# Final-V-0_1.net
KiCad netlist of a schematic drawn in EAGLE
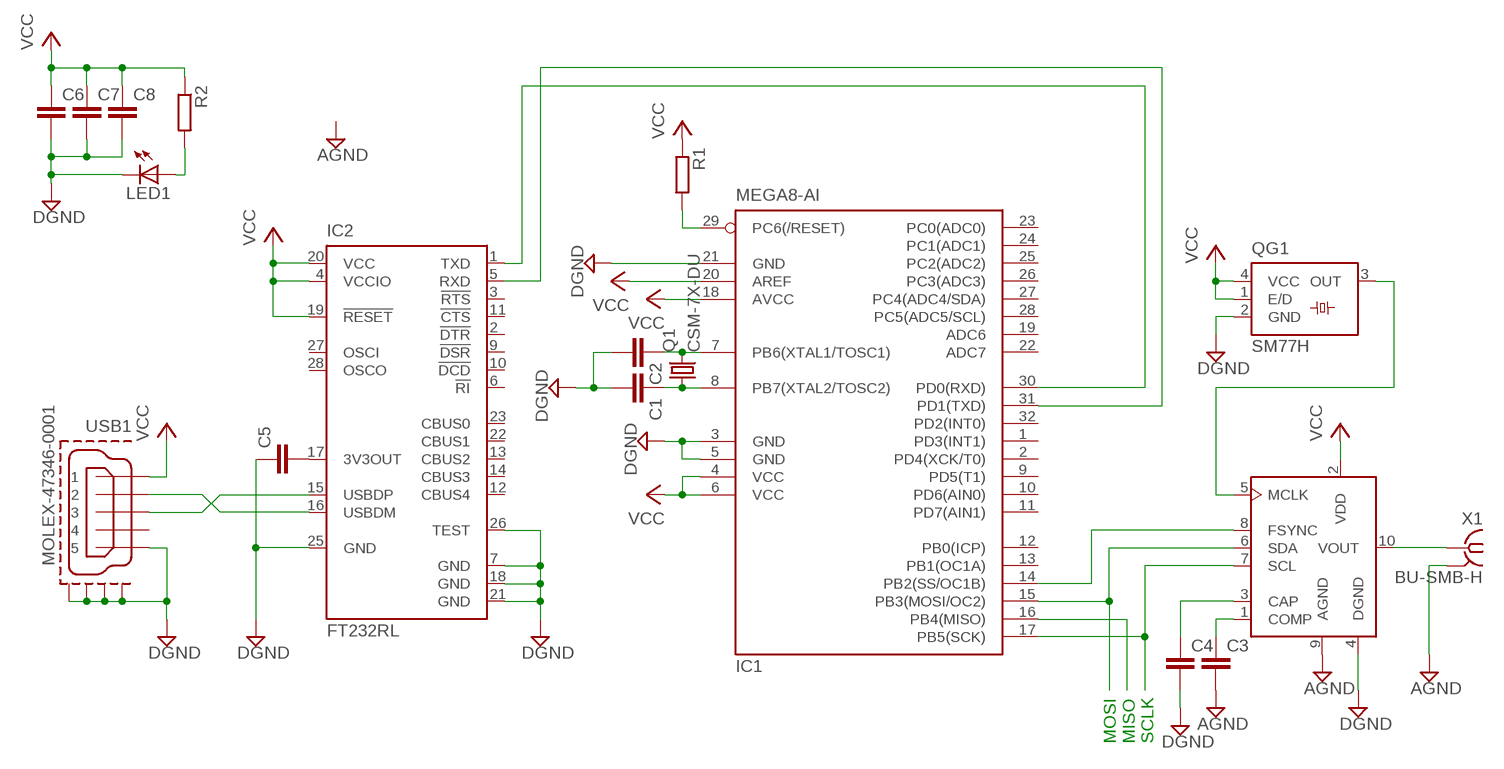
[diagram p0: schematic, sheet 1]

(export (version "E")
  (design (tool "Eeschema 10.0.6"))
  (components
    (comp (ref "C1")
      (value "C-EUC1206K")
      (footprint "eagle-import:C1206K")
      (libsource (lib "eagle-import") (part "C-EUC1206K"))
    )
    (comp (ref "C2")
      (value "C-EUC1206K")
      (footprint "eagle-import:C1206K")
      (libsource (lib "eagle-import") (part "C-EUC1206K"))
    )
    (comp (ref "C3")
      (value "C-EUC1206K")
      (footprint "eagle-import:C1206K")
      (libsource (lib "eagle-import") (part "C-EUC1206K"))
    )
    (comp (ref "C4")
      (value "C-EUC1206K")
      (footprint "eagle-import:C1206K")
      (libsource (lib "eagle-import") (part "C-EUC1206K"))
    )
    (comp (ref "C5")
      (value "C-EUC1206K")
      (footprint "eagle-import:C1206K")
      (libsource (lib "eagle-import") (part "C-EUC1206K"))
    )
    (comp (ref "C6")
      (value "C-EUC1206K")
      (footprint "eagle-import:C1206K")
      (libsource (lib "eagle-import") (part "C-EUC1206K"))
    )
    (comp (ref "C7")
      (value "C-EUC1206K")
      (footprint "eagle-import:C1206K")
      (libsource (lib "eagle-import") (part "C-EUC1206K"))
    )
    (comp (ref "C8")
      (value "C-EUC1206K")
      (footprint "eagle-import:C1206K")
      (libsource (lib "eagle-import") (part "C-EUC1206K"))
    )
    (comp (ref "IC1")
      (value "MEGA8-AI")
      (footprint "eagle-import:TQFP32-08")
      (fields (field (name "MPN") "ATMEGA8-16AU"))
      (libsource (lib "eagle-import") (part "MEGA8-AI"))
    )
    (comp (ref "IC2")
      (value "FT232RL")
      (footprint "eagle-import:SSOP28")
      (libsource (lib "eagle-import") (part "FT232RL"))
    )
    (comp (ref "LED1")
      (value "LEDSML1206")
      (footprint "eagle-import:SML1206")
      (libsource (lib "eagle-import") (part "LEDSML1206"))
    )
    (comp (ref "Q1")
      (value "CSM-7X-DU")
      (footprint "eagle-import:CSM-7X-DU")
      (libsource (lib "eagle-import") (part "CSM-7X-DU"))
    )
    (comp (ref "QG1")
      (value "SM77H")
      (footprint "eagle-import:SM77H")
      (libsource (lib "eagle-import") (part "SM77H"))
    )
    (comp (ref "R1")
      (value "R-EU_M1206")
      (footprint "eagle-import:M1206")
      (libsource (lib "eagle-import") (part "R-EU_M1206"))
    )
    (comp (ref "R2")
      (value "R-EU_M1206")
      (footprint "eagle-import:M1206")
      (libsource (lib "eagle-import") (part "R-EU_M1206"))
    )
    (comp (ref "U$1")
      (value "AD9833-SMD")
      (footprint "eagle-import:MSOP10")
      (libsource (lib "eagle-import") (part "AD9833-SMD"))
    )
    (comp (ref "USB1")
      (value "MOLEX-47346-0001")
      (footprint "eagle-import:MOLEX-47364-0001")
      (libsource (lib "eagle-import") (part "MOLEX-47346-0001"))
    )
    (comp (ref "X1")
      (value "BU-SMB-H")
      (footprint "eagle-import:BU-SMB-H")
      (libsource (lib "eagle-import") (part "BU-SMB-H"))
    )
  )
  (nets
    (net (code "1") (name "AGND") (class "Default")
      (node (ref "C3") (pin "2") (pinfunction "2_2") (pintype "passive"))
      (node (ref "U$1") (pin "9") (pinfunction "AGND_9") (pintype "bidirectional"))
      (node (ref "X1") (pin "2") (pinfunction "2_2") (pintype "passive"))
      (node (ref "X1") (pin "3") (pinfunction "2_3") (pintype "passive"))
      (node (ref "X1") (pin "4") (pinfunction "2_4") (pintype "passive"))
      (node (ref "X1") (pin "5") (pinfunction "2_5") (pintype "passive"))
    )
    (net (code "2") (name "DGND") (class "Default")
      (node (ref "C1") (pin "2") (pinfunction "2_2") (pintype "passive"))
      (node (ref "C2") (pin "2") (pinfunction "2_2") (pintype "passive"))
      (node (ref "C4") (pin "2") (pinfunction "2_2") (pintype "passive"))
      (node (ref "C5") (pin "1") (pinfunction "1_1") (pintype "passive"))
      (node (ref "C6") (pin "2") (pinfunction "2_2") (pintype "passive"))
      (node (ref "C7") (pin "2") (pinfunction "2_2") (pintype "passive"))
      (node (ref "C8") (pin "2") (pinfunction "2_2") (pintype "passive"))
      (node (ref "IC1") (pin "21") (pinfunction "GND_21") (pintype "power_in"))
      (node (ref "IC1") (pin "3") (pinfunction "GND_3") (pintype "power_in"))
      (node (ref "IC1") (pin "5") (pinfunction "GND_5") (pintype "power_in"))
      (node (ref "IC2") (pin "18") (pinfunction "GND_18") (pintype "power_in"))
      (node (ref "IC2") (pin "21") (pinfunction "GND_21") (pintype "power_in"))
      (node (ref "IC2") (pin "25") (pinfunction "GND_25") (pintype "power_in"))
      (node (ref "IC2") (pin "26") (pinfunction "TEST_26") (pintype "input"))
      (node (ref "IC2") (pin "7") (pinfunction "GND_7") (pintype "power_in"))
      (node (ref "LED1") (pin "C") (pinfunction "C_C") (pintype "passive"))
      (node (ref "QG1") (pin "2") (pinfunction "GND_2") (pintype "power_in"))
      (node (ref "U$1") (pin "4") (pinfunction "DGND_4") (pintype "bidirectional"))
      (node (ref "USB1") (pin "5") (pinfunction "5_5") (pintype "input"))
      (node (ref "USB1") (pin "GND1") (pinfunction "GND1_GND1") (pintype "bidirectional"))
      (node (ref "USB1") (pin "GND2") (pinfunction "GND2_GND2") (pintype "bidirectional"))
      (node (ref "USB1") (pin "GND3") (pinfunction "GND3_GND3") (pintype "bidirectional"))
      (node (ref "USB1") (pin "GND4") (pinfunction "GND4_GND4") (pintype "bidirectional"))
    )
    (net (code "3") (name "Net-(IC1-PB2(SS{slash}OC1B))") (class "Default")
      (node (ref "IC1") (pin "14") (pinfunction "PB2(SS/OC1B)_14") (pintype "bidirectional"))
      (node (ref "U$1") (pin "8") (pinfunction "FSYNC_8") (pintype "bidirectional"))
    )
    (net (code "4") (name "Net-(IC1-PB3(MOSI{slash}OC2))") (class "Default")
      (node (ref "IC1") (pin "15") (pinfunction "PB3(MOSI/OC2)_15") (pintype "bidirectional"))
      (node (ref "U$1") (pin "6") (pinfunction "SDA_6") (pintype "bidirectional"))
    )
    (net (code "5") (name "Net-(IC1-PB5(SCK))") (class "Default")
      (node (ref "IC1") (pin "17") (pinfunction "PB5(SCK)_17") (pintype "bidirectional"))
      (node (ref "U$1") (pin "7") (pinfunction "SCL_7") (pintype "bidirectional"))
    )
    (net (code "6") (name "Net-(IC1-PB6(XTAL1{slash}TOSC1))") (class "Default")
      (node (ref "C2") (pin "1") (pinfunction "1_1") (pintype "passive"))
      (node (ref "IC1") (pin "7") (pinfunction "PB6(XTAL1/TOSC1)_7") (pintype "bidirectional"))
      (node (ref "Q1") (pin "2") (pinfunction "2_2") (pintype "passive"))
    )
    (net (code "7") (name "Net-(IC1-PB7(XTAL2{slash}TOSC2))") (class "Default")
      (node (ref "C1") (pin "1") (pinfunction "1_1") (pintype "passive"))
      (node (ref "IC1") (pin "8") (pinfunction "PB7(XTAL2/TOSC2)_8") (pintype "bidirectional"))
      (node (ref "Q1") (pin "1") (pinfunction "1_1") (pintype "passive"))
    )
    (net (code "8") (name "Net-(IC1-PC6({slash}RESET))") (class "Default")
      (node (ref "IC1") (pin "29") (pinfunction "PC6(/RESET)_29") (pintype "bidirectional"))
      (node (ref "R1") (pin "2") (pinfunction "2_2") (pintype "passive"))
    )
    (net (code "9") (name "Net-(IC1-PD0(RXD))") (class "Default")
      (node (ref "IC1") (pin "30") (pinfunction "PD0(RXD)_30") (pintype "bidirectional"))
      (node (ref "IC2") (pin "1") (pinfunction "TXD_1") (pintype "output"))
    )
    (net (code "10") (name "Net-(IC1-PD1(TXD))") (class "Default")
      (node (ref "IC1") (pin "31") (pinfunction "PD1(TXD)_31") (pintype "bidirectional"))
      (node (ref "IC2") (pin "5") (pinfunction "RXD_5") (pintype "input"))
    )
    (net (code "11") (name "Net-(IC2-3V3OUT)") (class "Default")
      (node (ref "C5") (pin "2") (pinfunction "2_2") (pintype "passive"))
      (node (ref "IC2") (pin "17") (pinfunction "3V3OUT_17") (pintype "output"))
    )
    (net (code "12") (name "Net-(IC2-USBDM)") (class "Default")
      (node (ref "IC2") (pin "16") (pinfunction "USBDM_16") (pintype "bidirectional"))
      (node (ref "USB1") (pin "2") (pinfunction "2_2") (pintype "input"))
    )
    (net (code "13") (name "Net-(IC2-USBDP)") (class "Default")
      (node (ref "IC2") (pin "15") (pinfunction "USBDP_15") (pintype "bidirectional"))
      (node (ref "USB1") (pin "3") (pinfunction "3_3") (pintype "input"))
    )
    (net (code "14") (name "Net-(LED1-PadA)") (class "Default")
      (node (ref "LED1") (pin "A") (pinfunction "A_A") (pintype "passive"))
      (node (ref "R2") (pin "2") (pinfunction "2_2") (pintype "passive"))
    )
    (net (code "15") (name "Net-(QG1-OUT)") (class "Default")
      (node (ref "QG1") (pin "3") (pinfunction "OUT_3") (pintype "output"))
      (node (ref "U$1") (pin "5") (pinfunction "MCLK_5") (pintype "bidirectional"))
    )
    (net (code "16") (name "Net-(U$1-CAP)") (class "Default")
      (node (ref "C4") (pin "1") (pinfunction "1_1") (pintype "passive"))
      (node (ref "U$1") (pin "3") (pinfunction "CAP_3") (pintype "bidirectional"))
    )
    (net (code "17") (name "Net-(U$1-COMP)") (class "Default")
      (node (ref "C3") (pin "1") (pinfunction "1_1") (pintype "passive"))
      (node (ref "U$1") (pin "1") (pinfunction "COMP_1") (pintype "bidirectional"))
    )
    (net (code "18") (name "Net-(U$1-VOUT)") (class "Default")
      (node (ref "U$1") (pin "10") (pinfunction "VOUT_10") (pintype "bidirectional"))
      (node (ref "X1") (pin "1") (pinfunction "1_1") (pintype "passive"))
    )
    (net (code "19") (name "VCC") (class "Default")
      (node (ref "C6") (pin "1") (pinfunction "1_1") (pintype "passive"))
      (node (ref "C7") (pin "1") (pinfunction "1_1") (pintype "passive"))
      (node (ref "C8") (pin "1") (pinfunction "1_1") (pintype "passive"))
      (node (ref "IC1") (pin "18") (pinfunction "AVCC_18") (pintype "power_in"))
      (node (ref "IC1") (pin "20") (pinfunction "AREF_20") (pintype "passive"))
      (node (ref "IC1") (pin "4") (pinfunction "VCC_4") (pintype "power_in"))
      (node (ref "IC1") (pin "6") (pinfunction "VCC_6") (pintype "power_in"))
      (node (ref "IC2") (pin "19") (pinfunction "~{RESET}_19") (pintype "input"))
      (node (ref "IC2") (pin "20") (pinfunction "VCC_20") (pintype "power_in"))
      (node (ref "IC2") (pin "4") (pinfunction "VCCIO_4") (pintype "power_in"))
      (node (ref "QG1") (pin "1") (pinfunction "E/D_1") (pintype "input"))
      (node (ref "QG1") (pin "4") (pinfunction "VCC_4") (pintype "power_in"))
      (node (ref "R1") (pin "1") (pinfunction "1_1") (pintype "passive"))
      (node (ref "R2") (pin "1") (pinfunction "1_1") (pintype "passive"))
      (node (ref "U$1") (pin "2") (pinfunction "VDD_2") (pintype "bidirectional"))
      (node (ref "USB1") (pin "1") (pinfunction "1_1") (pintype "input"))
    )
    (net (code "20") (name "unconnected-(IC1-ADC6-Pad19)") (class "Default")
      (node (ref "IC1") (pin "19") (pinfunction "ADC6_19") (pintype "bidirectional"))
    )
    (net (code "21") (name "unconnected-(IC1-ADC7-Pad22)") (class "Default")
      (node (ref "IC1") (pin "22") (pinfunction "ADC7_22") (pintype "bidirectional"))
    )
    (net (code "22") (name "unconnected-(IC1-PB0(ICP)-Pad12)") (class "Default")
      (node (ref "IC1") (pin "12") (pinfunction "PB0(ICP)_12") (pintype "bidirectional"))
    )
    (net (code "23") (name "unconnected-(IC1-PB1(OC1A)-Pad13)") (class "Default")
      (node (ref "IC1") (pin "13") (pinfunction "PB1(OC1A)_13") (pintype "bidirectional"))
    )
    (net (code "24") (name "unconnected-(IC1-PB4(MISO)-Pad16)") (class "Default")
      (node (ref "IC1") (pin "16") (pinfunction "PB4(MISO)_16") (pintype "bidirectional"))
    )
    (net (code "25") (name "unconnected-(IC1-PC0(ADC0)-Pad23)") (class "Default")
      (node (ref "IC1") (pin "23") (pinfunction "PC0(ADC0)_23") (pintype "bidirectional"))
    )
    (net (code "26") (name "unconnected-(IC1-PC1(ADC1)-Pad24)") (class "Default")
      (node (ref "IC1") (pin "24") (pinfunction "PC1(ADC1)_24") (pintype "bidirectional"))
    )
    (net (code "27") (name "unconnected-(IC1-PC2(ADC2)-Pad25)") (class "Default")
      (node (ref "IC1") (pin "25") (pinfunction "PC2(ADC2)_25") (pintype "bidirectional"))
    )
    (net (code "28") (name "unconnected-(IC1-PC3(ADC3)-Pad26)") (class "Default")
      (node (ref "IC1") (pin "26") (pinfunction "PC3(ADC3)_26") (pintype "bidirectional"))
    )
    (net (code "29") (name "unconnected-(IC1-PC4(ADC4{slash}SDA)-Pad27)") (class "Default")
      (node (ref "IC1") (pin "27") (pinfunction "PC4(ADC4/SDA)_27") (pintype "bidirectional"))
    )
    (net (code "30") (name "unconnected-(IC1-PC5(ADC5{slash}SCL)-Pad28)") (class "Default")
      (node (ref "IC1") (pin "28") (pinfunction "PC5(ADC5/SCL)_28") (pintype "bidirectional"))
    )
    (net (code "31") (name "unconnected-(IC1-PD2(INT0)-Pad32)") (class "Default")
      (node (ref "IC1") (pin "32") (pinfunction "PD2(INT0)_32") (pintype "bidirectional"))
    )
    (net (code "32") (name "unconnected-(IC1-PD3(INT1)-Pad1)") (class "Default")
      (node (ref "IC1") (pin "1") (pinfunction "PD3(INT1)_1") (pintype "bidirectional"))
    )
    (net (code "33") (name "unconnected-(IC1-PD4(XCK{slash}T0)-Pad2)") (class "Default")
      (node (ref "IC1") (pin "2") (pinfunction "PD4(XCK/T0)_2") (pintype "bidirectional"))
    )
    (net (code "34") (name "unconnected-(IC1-PD5(T1)-Pad9)") (class "Default")
      (node (ref "IC1") (pin "9") (pinfunction "PD5(T1)_9") (pintype "bidirectional"))
    )
    (net (code "35") (name "unconnected-(IC1-PD6(AIN0)-Pad10)") (class "Default")
      (node (ref "IC1") (pin "10") (pinfunction "PD6(AIN0)_10") (pintype "bidirectional"))
    )
    (net (code "36") (name "unconnected-(IC1-PD7(AIN1)-Pad11)") (class "Default")
      (node (ref "IC1") (pin "11") (pinfunction "PD7(AIN1)_11") (pintype "bidirectional"))
    )
    (net (code "37") (name "unconnected-(IC2-CBUS0-Pad23)") (class "Default")
      (node (ref "IC2") (pin "23") (pinfunction "CBUS0_23") (pintype "bidirectional"))
    )
    (net (code "38") (name "unconnected-(IC2-CBUS1-Pad22)") (class "Default")
      (node (ref "IC2") (pin "22") (pinfunction "CBUS1_22") (pintype "bidirectional"))
    )
    (net (code "39") (name "unconnected-(IC2-CBUS2-Pad13)") (class "Default")
      (node (ref "IC2") (pin "13") (pinfunction "CBUS2_13") (pintype "bidirectional"))
    )
    (net (code "40") (name "unconnected-(IC2-CBUS3-Pad14)") (class "Default")
      (node (ref "IC2") (pin "14") (pinfunction "CBUS3_14") (pintype "bidirectional"))
    )
    (net (code "41") (name "unconnected-(IC2-CBUS4-Pad12)") (class "Default")
      (node (ref "IC2") (pin "12") (pinfunction "CBUS4_12") (pintype "bidirectional"))
    )
    (net (code "42") (name "unconnected-(IC2-OSCI-Pad27)") (class "Default")
      (node (ref "IC2") (pin "27") (pinfunction "OSCI_27") (pintype "input"))
    )
    (net (code "43") (name "unconnected-(IC2-OSCO-Pad28)") (class "Default")
      (node (ref "IC2") (pin "28") (pinfunction "OSCO_28") (pintype "output"))
    )
    (net (code "44") (name "unconnected-(IC2-~{CTS}-Pad11)") (class "Default")
      (node (ref "IC2") (pin "11") (pinfunction "~{CTS}_11") (pintype "input"))
    )
    (net (code "45") (name "unconnected-(IC2-~{DCD}-Pad10)") (class "Default")
      (node (ref "IC2") (pin "10") (pinfunction "~{DCD}_10") (pintype "input"))
    )
    (net (code "46") (name "unconnected-(IC2-~{DSR}-Pad9)") (class "Default")
      (node (ref "IC2") (pin "9") (pinfunction "~{DSR}_9") (pintype "input"))
    )
    (net (code "47") (name "unconnected-(IC2-~{DTR}-Pad2)") (class "Default")
      (node (ref "IC2") (pin "2") (pinfunction "~{DTR}_2") (pintype "output"))
    )
    (net (code "48") (name "unconnected-(IC2-~{RI}-Pad6)") (class "Default")
      (node (ref "IC2") (pin "6") (pinfunction "~{RI}_6") (pintype "input"))
    )
    (net (code "49") (name "unconnected-(IC2-~{RTS}-Pad3)") (class "Default")
      (node (ref "IC2") (pin "3") (pinfunction "~{RTS}_3") (pintype "output"))
    )
    (net (code "50") (name "unconnected-(USB1-Pad4)") (class "Default")
      (node (ref "USB1") (pin "4") (pinfunction "4_4") (pintype "input"))
    )
  )
)
